# TelescopeGoTo_MKII.net
KiCad netlist of a schematic drawn in EasyEDA
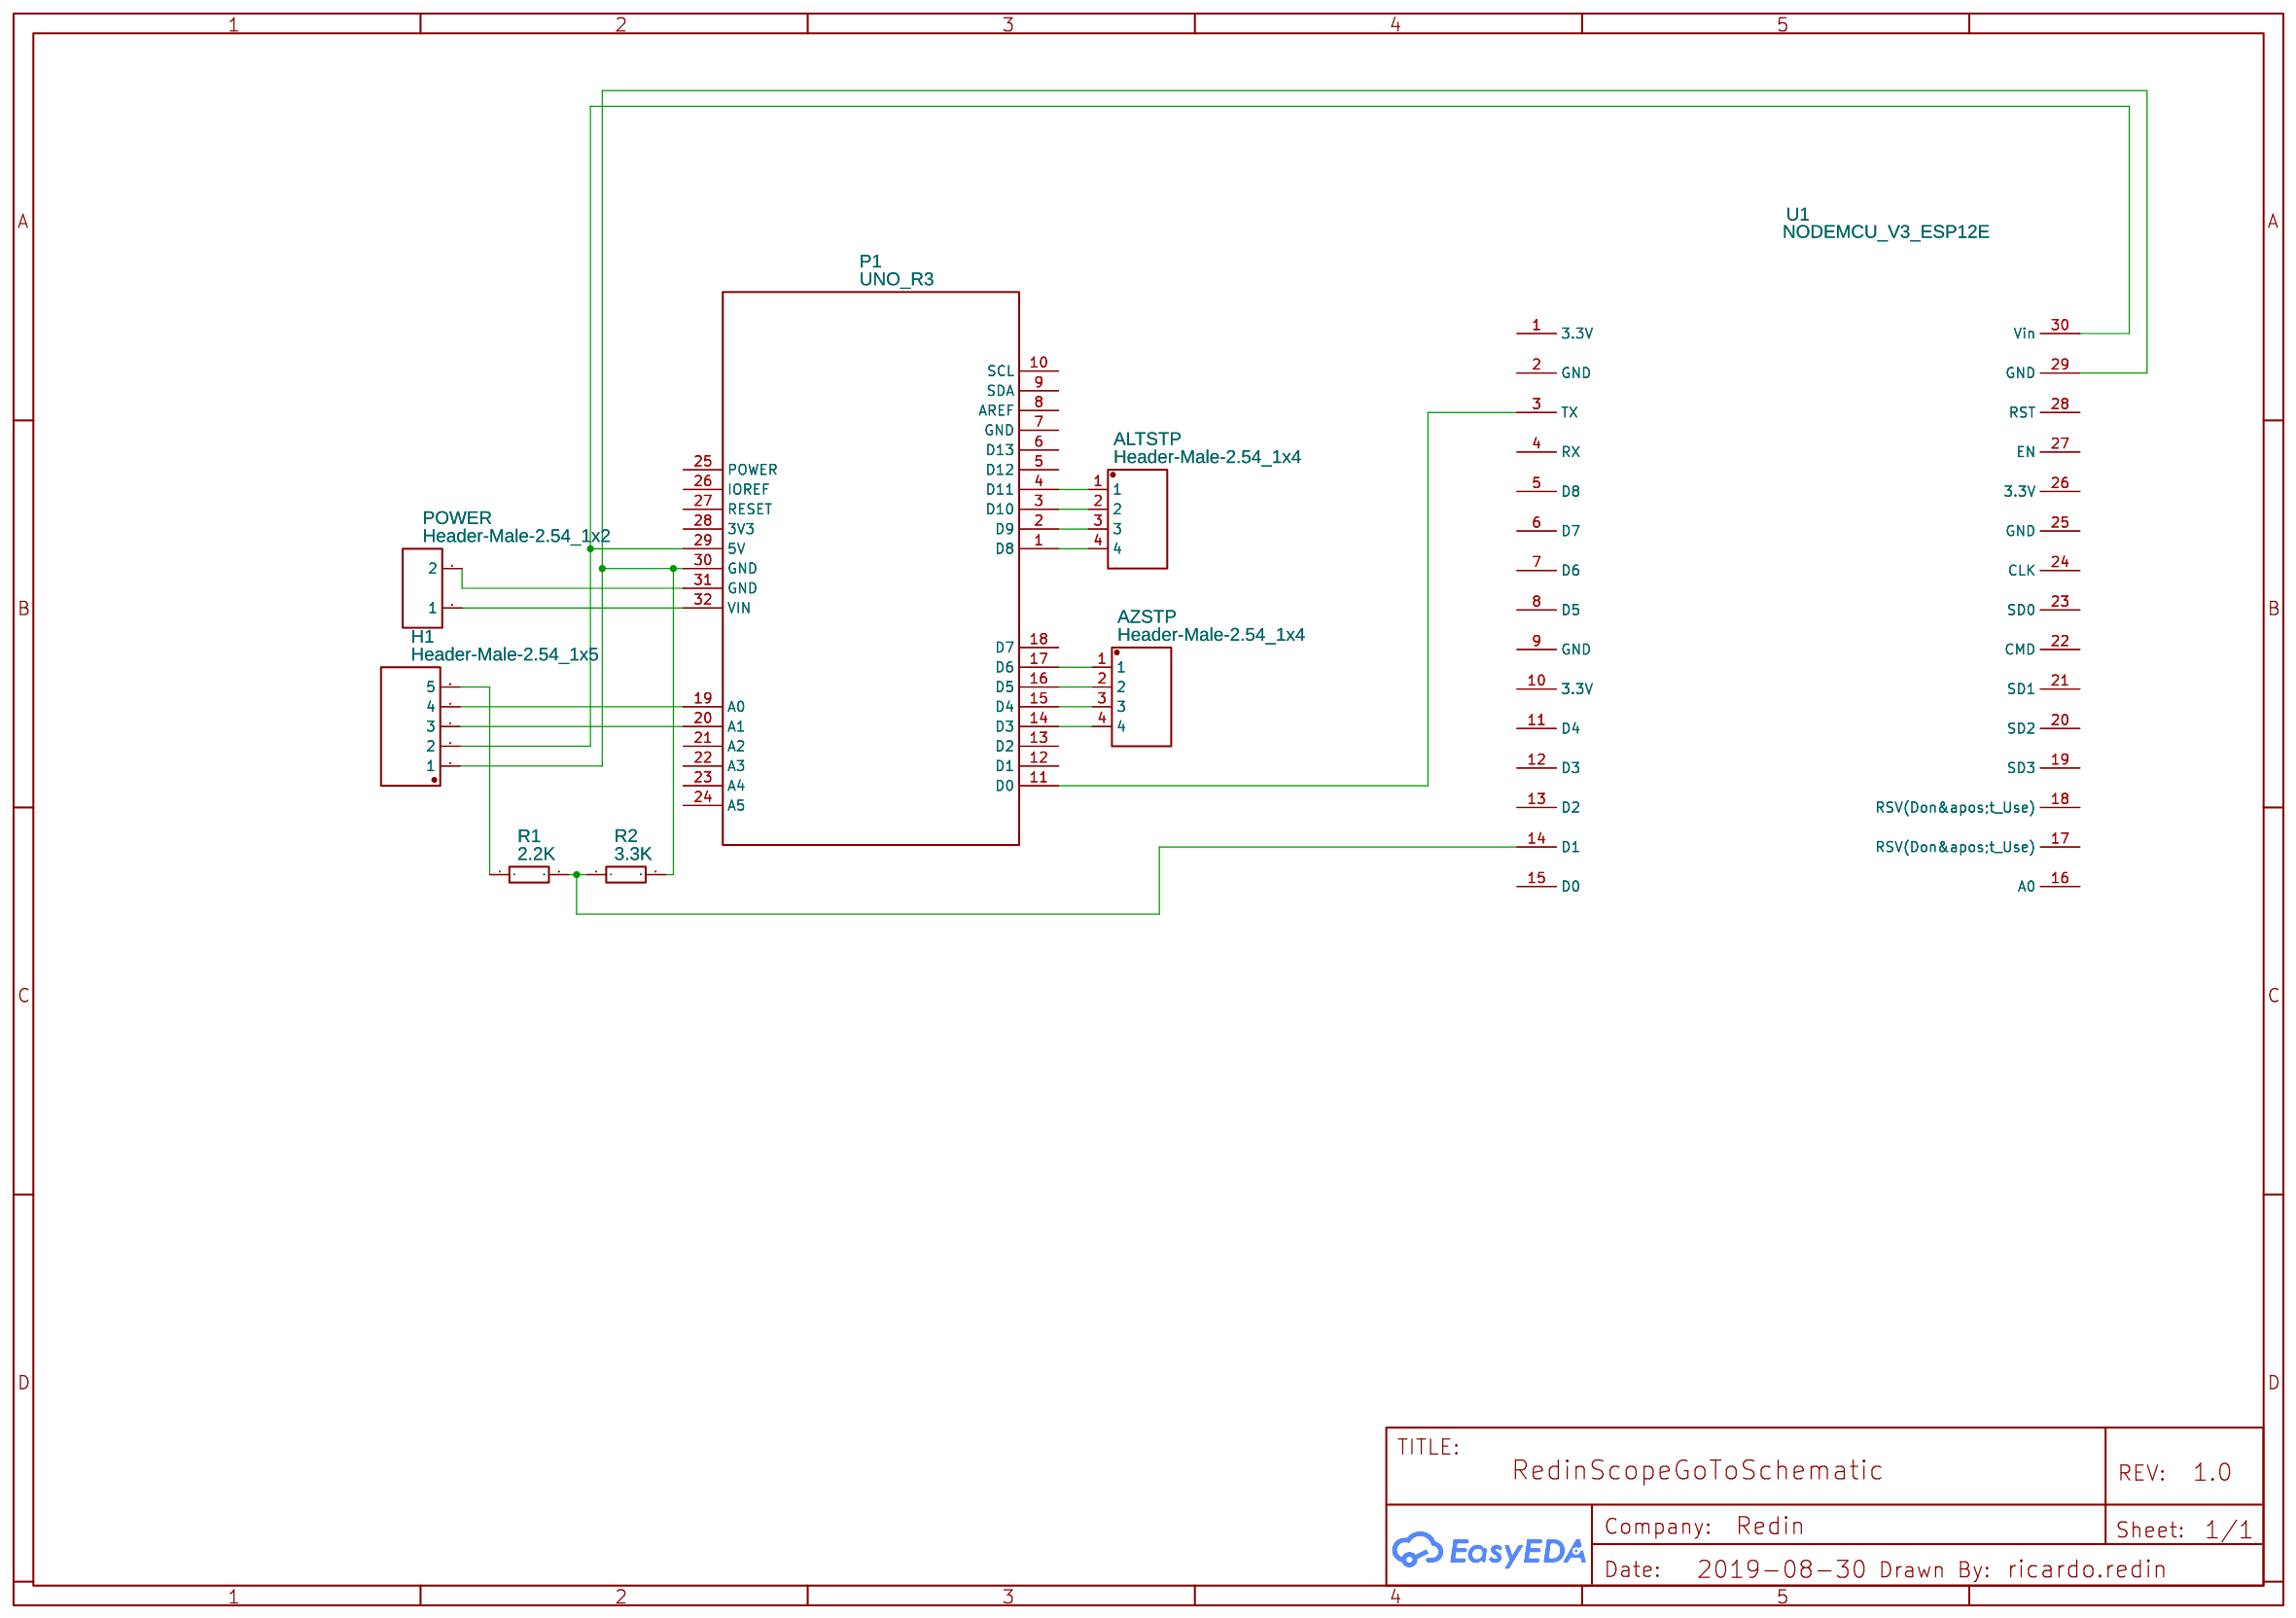
[diagram p0: schematic sheet]

(export (version "E")
  (design (tool "Eeschema 10.0.6"))
  (components
    (comp (ref "ALTSTP")
      (value "Header-Male-2.54_1x4")
      (fields
        (field (name "BOM_Manufacturer Part") "210S-1*4P L=11.6MMGold-plated black")
        (field (name "BOM_Supplier Part") "C124378")
      )
      (libsource (lib "") (part "Unknown_564_256"))
    )
    (comp (ref "AZSTP")
      (value "Header-Male-2.54_1x4")
      (fields
        (field (name "BOM_Manufacturer Part") "210S-1*4P L=11.6MMGold-plated black")
        (field (name "BOM_Supplier Part") "C124378")
      )
      (libsource (lib "") (part "Unknown_566_346"))
    )
    (comp (ref "H1")
      (value "Header-Male-2.54_1x5")
      (fields
        (field (name "BOM_Manufacturer Part") "210S-1*5P L=11.6MMGold-plated black")
        (field (name "BOM_Supplier Part") "C124379")
      )
      (libsource (lib "") (part "Unknown_206_361"))
    )
    (comp (ref "P1") (value "UNO_R3") (libsource (lib "") (part "Unknown_434_281")))
    (comp (ref "POWER")
      (value "Header-Male-2.54_1x2")
      (fields (field (name "BOM_Manufacturer Part") "826629-2") (field (name "BOM_Supplier Part") "C86471"))
      (libsource (lib "") (part "Unknown_212_291"))
    )
    (comp (ref "R1")
      (value "2.2K")
      (fields
        (field (name "BOM_Manufacturer Part") "0805W8F2201T5E")
        (field (name "BOM_Supplier Part") "C17520")
      )
      (libsource (lib "") (part "0805W8F2201T5E"))
    )
    (comp (ref "R2")
      (value "3.3K")
      (fields
        (field (name "BOM_Manufacturer Part") "0805W8F3301T5E")
        (field (name "BOM_Supplier Part") "C26010")
      )
      (libsource (lib "") (part "0805W8F3301T5E"))
    )
    (comp (ref "U1")
      (value "NODEMCU_V3_ESP12E")
      (fields (field (name "BOM_Manufacturer Part") "NODEMCU") (field (name "BOM_Supplier Part") "ESP12E"))
      (libsource (lib "") (part "NODEMCU_V3_ESP12E"))
    )
  )
  (nets
    (net (code "1") (name "Net-(H1-Pad1)") (class "Default")
      (node (ref "H1") (pin "1") (pinfunction "1_1") (pintype "unspecified"))
      (node (ref "P1") (pin "30") (pinfunction "GND_30") (pintype "unspecified"))
      (node (ref "R2") (pin "2") (pinfunction "2_2") (pintype "input"))
      (node (ref "U1") (pin "29") (pinfunction "GND_29") (pintype "unspecified"))
    )
    (net (code "2") (name "Net-(H1-Pad5)") (class "Default")
      (node (ref "H1") (pin "5") (pinfunction "5_5") (pintype "unspecified"))
      (node (ref "R1") (pin "1") (pinfunction "1_1") (pintype "input"))
    )
    (net (code "3") (name "Net-(P1-5V)") (class "Default")
      (node (ref "H1") (pin "2") (pinfunction "2_2") (pintype "unspecified"))
      (node (ref "P1") (pin "29") (pinfunction "5V_29") (pintype "unspecified"))
      (node (ref "U1") (pin "30") (pinfunction "Vin_30") (pintype "unspecified"))
    )
    (net (code "4") (name "Net-(P1-A0)") (class "Default")
      (node (ref "H1") (pin "4") (pinfunction "4_4") (pintype "unspecified"))
      (node (ref "P1") (pin "19") (pinfunction "A0_19") (pintype "unspecified"))
    )
    (net (code "5") (name "Net-(P1-A1)") (class "Default")
      (node (ref "H1") (pin "3") (pinfunction "3_3") (pintype "unspecified"))
      (node (ref "P1") (pin "20") (pinfunction "A1_20") (pintype "unspecified"))
    )
    (net (code "6") (name "Net-(P1-D0)") (class "Default")
      (node (ref "P1") (pin "11") (pinfunction "D0_11") (pintype "unspecified"))
      (node (ref "U1") (pin "3") (pinfunction "TX_3") (pintype "unspecified"))
    )
    (net (code "7") (name "Net-(P1-D3)") (class "Default")
      (node (ref "AZSTP") (pin "4") (pinfunction "4_4") (pintype "unspecified"))
      (node (ref "P1") (pin "14") (pinfunction "D3_14") (pintype "unspecified"))
    )
    (net (code "8") (name "Net-(P1-D4)") (class "Default")
      (node (ref "AZSTP") (pin "3") (pinfunction "3_3") (pintype "unspecified"))
      (node (ref "P1") (pin "15") (pinfunction "D4_15") (pintype "unspecified"))
    )
    (net (code "9") (name "Net-(P1-D5)") (class "Default")
      (node (ref "AZSTP") (pin "2") (pinfunction "2_2") (pintype "unspecified"))
      (node (ref "P1") (pin "16") (pinfunction "D5_16") (pintype "unspecified"))
    )
    (net (code "10") (name "Net-(P1-D6)") (class "Default")
      (node (ref "AZSTP") (pin "1") (pinfunction "1_1") (pintype "unspecified"))
      (node (ref "P1") (pin "17") (pinfunction "D6_17") (pintype "unspecified"))
    )
    (net (code "11") (name "Net-(P1-D8)") (class "Default")
      (node (ref "ALTSTP") (pin "4") (pinfunction "4_4") (pintype "unspecified"))
      (node (ref "P1") (pin "1") (pinfunction "D8_1") (pintype "unspecified"))
    )
    (net (code "12") (name "Net-(P1-D9)") (class "Default")
      (node (ref "ALTSTP") (pin "3") (pinfunction "3_3") (pintype "unspecified"))
      (node (ref "P1") (pin "2") (pinfunction "D9_2") (pintype "unspecified"))
    )
    (net (code "13") (name "Net-(P1-D10)") (class "Default")
      (node (ref "ALTSTP") (pin "2") (pinfunction "2_2") (pintype "unspecified"))
      (node (ref "P1") (pin "3") (pinfunction "D10_3") (pintype "unspecified"))
    )
    (net (code "14") (name "Net-(P1-D11)") (class "Default")
      (node (ref "ALTSTP") (pin "1") (pinfunction "1_1") (pintype "unspecified"))
      (node (ref "P1") (pin "4") (pinfunction "D11_4") (pintype "unspecified"))
    )
    (net (code "15") (name "Net-(P1-GND-Pad31)") (class "Default")
      (node (ref "P1") (pin "31") (pinfunction "GND_31") (pintype "unspecified"))
      (node (ref "POWER") (pin "2") (pinfunction "2_2") (pintype "unspecified"))
    )
    (net (code "16") (name "Net-(P1-VIN)") (class "Default")
      (node (ref "P1") (pin "32") (pinfunction "VIN_32") (pintype "unspecified"))
      (node (ref "POWER") (pin "1") (pinfunction "1_1") (pintype "unspecified"))
    )
    (net (code "17") (name "Net-(U1-D1)") (class "Default")
      (node (ref "R1") (pin "2") (pinfunction "2_2") (pintype "input"))
      (node (ref "R2") (pin "1") (pinfunction "1_1") (pintype "input"))
      (node (ref "U1") (pin "14") (pinfunction "D1_14") (pintype "unspecified"))
    )
    (net (code "18") (name "unconnected-(P1-3V3-Pad28)") (class "Default")
      (node (ref "P1") (pin "28") (pinfunction "3V3_28") (pintype "unspecified"))
    )
    (net (code "19") (name "unconnected-(P1-A2-Pad21)") (class "Default")
      (node (ref "P1") (pin "21") (pinfunction "A2_21") (pintype "unspecified"))
    )
    (net (code "20") (name "unconnected-(P1-A3-Pad22)") (class "Default")
      (node (ref "P1") (pin "22") (pinfunction "A3_22") (pintype "unspecified"))
    )
    (net (code "21") (name "unconnected-(P1-A4-Pad23)") (class "Default")
      (node (ref "P1") (pin "23") (pinfunction "A4_23") (pintype "unspecified"))
    )
    (net (code "22") (name "unconnected-(P1-A5-Pad24)") (class "Default")
      (node (ref "P1") (pin "24") (pinfunction "A5_24") (pintype "unspecified"))
    )
    (net (code "23") (name "unconnected-(P1-AREF-Pad8)") (class "Default")
      (node (ref "P1") (pin "8") (pinfunction "AREF_8") (pintype "unspecified"))
    )
    (net (code "24") (name "unconnected-(P1-D1-Pad12)") (class "Default")
      (node (ref "P1") (pin "12") (pinfunction "D1_12") (pintype "unspecified"))
    )
    (net (code "25") (name "unconnected-(P1-D2-Pad13)") (class "Default")
      (node (ref "P1") (pin "13") (pinfunction "D2_13") (pintype "unspecified"))
    )
    (net (code "26") (name "unconnected-(P1-D7-Pad18)") (class "Default")
      (node (ref "P1") (pin "18") (pinfunction "D7_18") (pintype "unspecified"))
    )
    (net (code "27") (name "unconnected-(P1-D12-Pad5)") (class "Default")
      (node (ref "P1") (pin "5") (pinfunction "D12_5") (pintype "unspecified"))
    )
    (net (code "28") (name "unconnected-(P1-D13-Pad6)") (class "Default")
      (node (ref "P1") (pin "6") (pinfunction "D13_6") (pintype "unspecified"))
    )
    (net (code "29") (name "unconnected-(P1-GND-Pad7)") (class "Default")
      (node (ref "P1") (pin "7") (pinfunction "GND_7") (pintype "unspecified"))
    )
    (net (code "30") (name "unconnected-(P1-IOREF-Pad26)") (class "Default")
      (node (ref "P1") (pin "26") (pinfunction "IOREF_26") (pintype "unspecified"))
    )
    (net (code "31") (name "unconnected-(P1-POWER-Pad25)") (class "Default")
      (node (ref "P1") (pin "25") (pinfunction "POWER_25") (pintype "unspecified"))
    )
    (net (code "32") (name "unconnected-(P1-RESET-Pad27)") (class "Default")
      (node (ref "P1") (pin "27") (pinfunction "RESET_27") (pintype "unspecified"))
    )
    (net (code "33") (name "unconnected-(P1-SCL-Pad10)") (class "Default")
      (node (ref "P1") (pin "10") (pinfunction "SCL_10") (pintype "unspecified"))
    )
    (net (code "34") (name "unconnected-(P1-SDA-Pad9)") (class "Default")
      (node (ref "P1") (pin "9") (pinfunction "SDA_9") (pintype "unspecified"))
    )
    (net (code "35") (name "unconnected-(U1-3.3V-Pad1)") (class "Default")
      (node (ref "U1") (pin "1") (pinfunction "3.3V_1") (pintype "unspecified"))
    )
    (net (code "36") (name "unconnected-(U1-3.3V-Pad10)") (class "Default")
      (node (ref "U1") (pin "10") (pinfunction "3.3V_10") (pintype "unspecified"))
    )
    (net (code "37") (name "unconnected-(U1-3.3V-Pad26)") (class "Default")
      (node (ref "U1") (pin "26") (pinfunction "3.3V_26") (pintype "unspecified"))
    )
    (net (code "38") (name "unconnected-(U1-A0-Pad16)") (class "Default")
      (node (ref "U1") (pin "16") (pinfunction "A0_16") (pintype "unspecified"))
    )
    (net (code "39") (name "unconnected-(U1-CLK-Pad24)") (class "Default")
      (node (ref "U1") (pin "24") (pinfunction "CLK_24") (pintype "unspecified"))
    )
    (net (code "40") (name "unconnected-(U1-CMD-Pad22)") (class "Default")
      (node (ref "U1") (pin "22") (pinfunction "CMD_22") (pintype "unspecified"))
    )
    (net (code "41") (name "unconnected-(U1-D0-Pad15)") (class "Default")
      (node (ref "U1") (pin "15") (pinfunction "D0_15") (pintype "unspecified"))
    )
    (net (code "42") (name "unconnected-(U1-D2-Pad13)") (class "Default")
      (node (ref "U1") (pin "13") (pinfunction "D2_13") (pintype "unspecified"))
    )
    (net (code "43") (name "unconnected-(U1-D3-Pad12)") (class "Default")
      (node (ref "U1") (pin "12") (pinfunction "D3_12") (pintype "unspecified"))
    )
    (net (code "44") (name "unconnected-(U1-D4-Pad11)") (class "Default")
      (node (ref "U1") (pin "11") (pinfunction "D4_11") (pintype "unspecified"))
    )
    (net (code "45") (name "unconnected-(U1-D5-Pad8)") (class "Default")
      (node (ref "U1") (pin "8") (pinfunction "D5_8") (pintype "unspecified"))
    )
    (net (code "46") (name "unconnected-(U1-D6-Pad7)") (class "Default")
      (node (ref "U1") (pin "7") (pinfunction "D6_7") (pintype "unspecified"))
    )
    (net (code "47") (name "unconnected-(U1-D7-Pad6)") (class "Default")
      (node (ref "U1") (pin "6") (pinfunction "D7_6") (pintype "unspecified"))
    )
    (net (code "48") (name "unconnected-(U1-D8-Pad5)") (class "Default")
      (node (ref "U1") (pin "5") (pinfunction "D8_5") (pintype "unspecified"))
    )
    (net (code "49") (name "unconnected-(U1-EN-Pad27)") (class "Default")
      (node (ref "U1") (pin "27") (pinfunction "EN_27") (pintype "unspecified"))
    )
    (net (code "50") (name "unconnected-(U1-GND-Pad2)") (class "Default")
      (node (ref "U1") (pin "2") (pinfunction "GND_2") (pintype "unspecified"))
    )
    (net (code "51") (name "unconnected-(U1-GND-Pad9)") (class "Default")
      (node (ref "U1") (pin "9") (pinfunction "GND_9") (pintype "unspecified"))
    )
    (net (code "52") (name "unconnected-(U1-GND-Pad25)") (class "Default")
      (node (ref "U1") (pin "25") (pinfunction "GND_25") (pintype "unspecified"))
    )
    (net (code "53") (name "unconnected-(U1-RST-Pad28)") (class "Default")
      (node (ref "U1") (pin "28") (pinfunction "RST_28") (pintype "unspecified"))
    )
    (net (code "54") (name "unconnected-(U1-RSV(Don&apos;t_Use)-Pad17)") (class "Default")
      (node (ref "U1") (pin "17") (pinfunction "RSV(Don&apos;t_Use)_17") (pintype "unspecified"))
    )
    (net (code "55") (name "unconnected-(U1-RSV(Don&apos;t_Use)-Pad18)") (class "Default")
      (node (ref "U1") (pin "18") (pinfunction "RSV(Don&apos;t_Use)_18") (pintype "unspecified"))
    )
    (net (code "56") (name "unconnected-(U1-RX-Pad4)") (class "Default")
      (node (ref "U1") (pin "4") (pinfunction "RX_4") (pintype "unspecified"))
    )
    (net (code "57") (name "unconnected-(U1-SD0-Pad23)") (class "Default")
      (node (ref "U1") (pin "23") (pinfunction "SD0_23") (pintype "unspecified"))
    )
    (net (code "58") (name "unconnected-(U1-SD1-Pad21)") (class "Default")
      (node (ref "U1") (pin "21") (pinfunction "SD1_21") (pintype "unspecified"))
    )
    (net (code "59") (name "unconnected-(U1-SD2-Pad20)") (class "Default")
      (node (ref "U1") (pin "20") (pinfunction "SD2_20") (pintype "unspecified"))
    )
    (net (code "60") (name "unconnected-(U1-SD3-Pad19)") (class "Default")
      (node (ref "U1") (pin "19") (pinfunction "SD3_19") (pintype "unspecified"))
    )
  )
)
